# 407-exp.net
KiCad netlist of a schematic drawn in Altium Designer
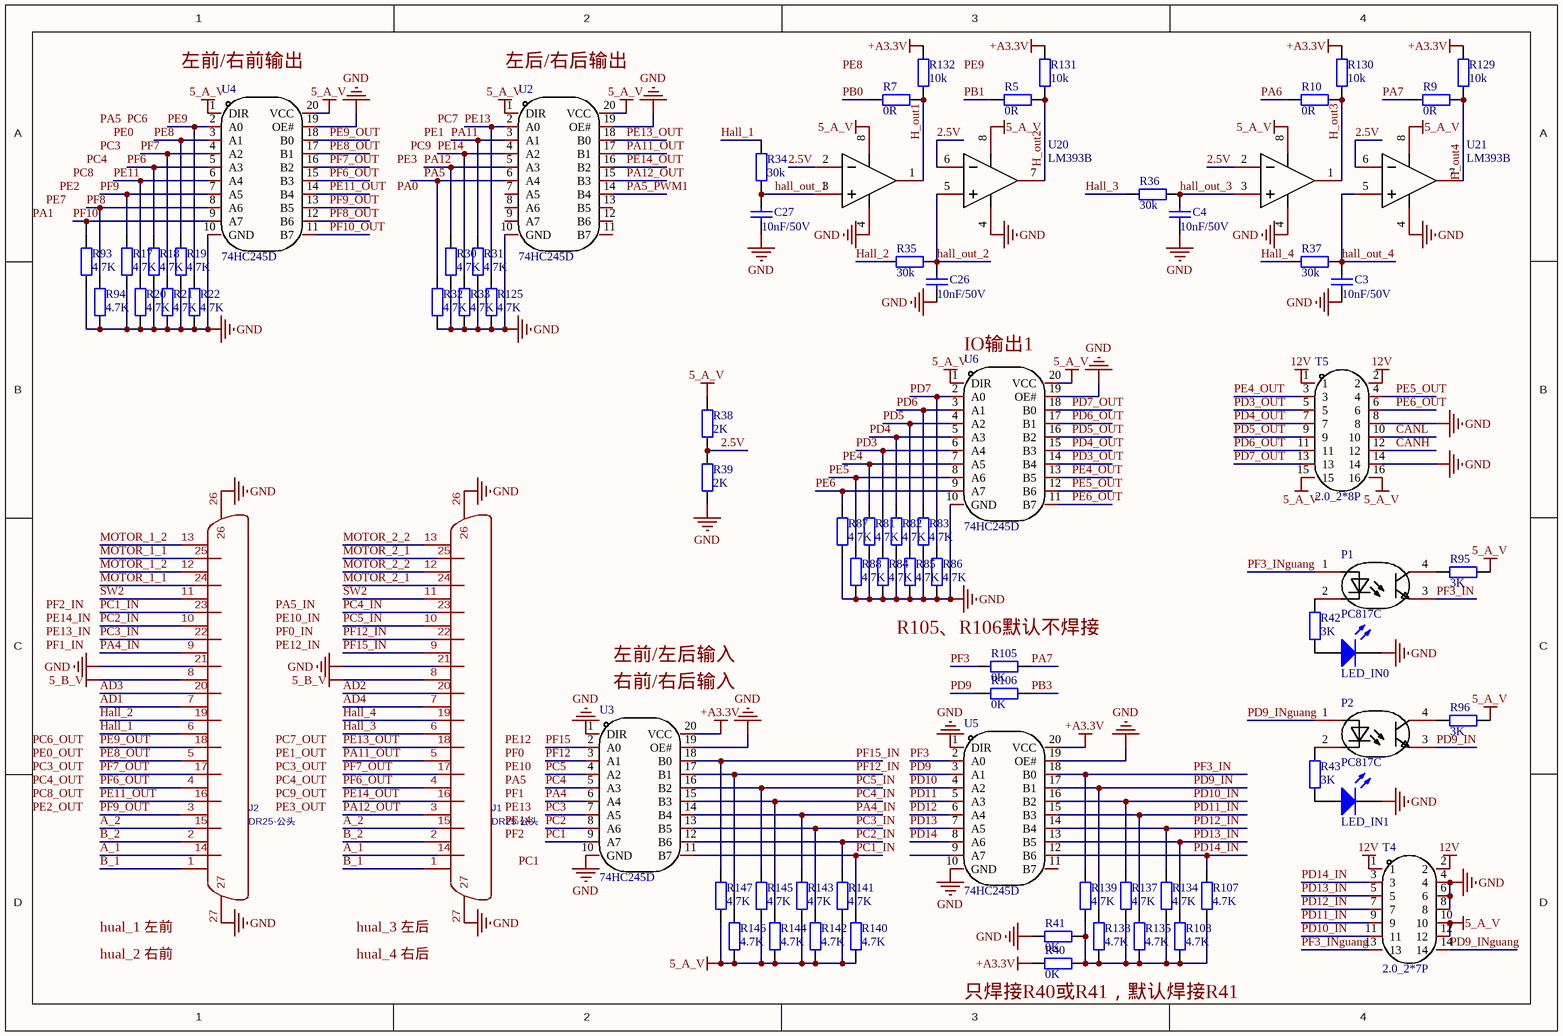
[diagram p0: 407-exp.schdoc]

(export (version "E")
  (design (tool "Eeschema 10.0.6"))
  (components
    (comp (ref "C3")
      (value "10nF/50V")
      (description "Capacitor")
      (fields (field (name "PUBLISHER") "Altium Limited"))
      (libsource (lib "Miscellaneous Devices") (part "Cap"))
    )
    (comp (ref "C4")
      (value "10nF/50V")
      (description "Capacitor")
      (fields (field (name "PUBLISHER") "Altium Limited"))
      (libsource (lib "Miscellaneous Devices") (part "Cap"))
    )
    (comp (ref "C26")
      (value "10nF/50V")
      (description "Capacitor")
      (fields (field (name "PUBLISHER") "Altium Limited"))
      (libsource (lib "Miscellaneous Devices") (part "Cap"))
    )
    (comp (ref "C27")
      (value "10nF/50V")
      (description "Capacitor")
      (fields (field (name "PUBLISHER") "Altium Limited"))
      (libsource (lib "Miscellaneous Devices") (part "Cap"))
    )
    (comp (ref "J1")
      (value "DR25-公头")
      (fields (field (name "MANUFACTURER PART") "DMR025PF000XH00") (field (name "CONTRIBUTOR") "MR_Peng888"))
      (libsource (lib "altium-import") (part "root_1_DR25-公头_"))
    )
    (comp (ref "J2")
      (value "DR25-公头")
      (fields (field (name "MANUFACTURER PART") "DMR025PF000XH00") (field (name "CONTRIBUTOR") "MR_Peng888"))
      (libsource (lib "altium-import") (part "root_1_DR25-公头_"))
    )
    (comp (ref "LED_IN0")
      (value "LED")
      (footprint "LED")
      (description "发光二极管")
      (libsource (lib "0.3 - LED发光二极管-IR二极管_接收管-光耦") (part "LED"))
    )
    (comp (ref "LED_IN1")
      (value "LED")
      (footprint "LED")
      (description "发光二极管")
      (libsource (lib "0.3 - LED发光二极管-IR二极管_接收管-光耦") (part "LED"))
    )
    (comp (ref "P1") (value "PC817C") (footprint "PC817C") (libsource (lib "tianjin_2023") (part "PC817C")))
    (comp (ref "P2") (value "PC817C") (footprint "PC817C") (libsource (lib "tianjin_2023") (part "PC817C")))
    (comp (ref "R5")
      (value "0R")
      (footprint "R0603_L")
      (description "Resistor")
      (fields (field (name "PUBLISHER") "Altium Limited"))
      (libsource (lib "MOS motor driving module ") (part "Res2"))
    )
    (comp (ref "R7")
      (value "0R")
      (footprint "R0603_L")
      (description "Resistor")
      (fields (field (name "PUBLISHER") "Altium Limited"))
      (libsource (lib "MOS motor driving module ") (part "Res2"))
    )
    (comp (ref "R9")
      (value "0R")
      (footprint "R0603_L")
      (description "Resistor")
      (fields (field (name "PUBLISHER") "Altium Limited"))
      (libsource (lib "MOS motor driving module ") (part "Res2"))
    )
    (comp (ref "R10")
      (value "0R")
      (footprint "R0603_L")
      (description "Resistor")
      (fields (field (name "PUBLISHER") "Altium Limited"))
      (libsource (lib "MOS motor driving module ") (part "Res2"))
    )
    (comp (ref "R17")
      (value "4.7K")
      (footprint "R0603_L")
      (description "Resistor")
      (fields (field (name "PUBLISHER") "Altium Limited"))
      (libsource (lib "") (part "Res2_1"))
    )
    (comp (ref "R18")
      (value "4.7K")
      (footprint "R0603_L")
      (description "Resistor")
      (fields (field (name "PUBLISHER") "Altium Limited"))
      (libsource (lib "") (part "Res2_1"))
    )
    (comp (ref "R19")
      (value "4.7K")
      (footprint "R0603_L")
      (description "Resistor")
      (fields (field (name "PUBLISHER") "Altium Limited"))
      (libsource (lib "") (part "Res2_1"))
    )
    (comp (ref "R20")
      (value "4.7K")
      (footprint "R0603_L")
      (description "Resistor")
      (fields (field (name "PUBLISHER") "Altium Limited"))
      (libsource (lib "") (part "Res2_1"))
    )
    (comp (ref "R21")
      (value "4.7K")
      (footprint "R0603_L")
      (description "Resistor")
      (fields (field (name "PUBLISHER") "Altium Limited"))
      (libsource (lib "") (part "Res2_1"))
    )
    (comp (ref "R22")
      (value "4.7K")
      (footprint "R0603_L")
      (description "Resistor")
      (fields (field (name "PUBLISHER") "Altium Limited"))
      (libsource (lib "") (part "Res2_1"))
    )
    (comp (ref "R30")
      (value "4.7K")
      (footprint "R0603_L")
      (description "Resistor")
      (fields (field (name "PUBLISHER") "Altium Limited"))
      (libsource (lib "") (part "Res2_1"))
    )
    (comp (ref "R31")
      (value "4.7K")
      (footprint "R0603_L")
      (description "Resistor")
      (fields (field (name "PUBLISHER") "Altium Limited"))
      (libsource (lib "") (part "Res2_1"))
    )
    (comp (ref "R32")
      (value "4.7K")
      (footprint "R0603_L")
      (description "Resistor")
      (fields (field (name "PUBLISHER") "Altium Limited"))
      (libsource (lib "") (part "Res2_1"))
    )
    (comp (ref "R33")
      (value "4.7K")
      (footprint "R0603_L")
      (description "Resistor")
      (fields (field (name "PUBLISHER") "Altium Limited"))
      (libsource (lib "") (part "Res2_1"))
    )
    (comp (ref "R34")
      (value "30k")
      (footprint "R0603_L")
      (description "Resistor")
      (fields (field (name "PUBLISHER") "Altium Limited"))
      (libsource (lib "") (part "Res2_2"))
    )
    (comp (ref "R35")
      (value "30k")
      (footprint "R0603_L")
      (description "Resistor")
      (fields (field (name "PUBLISHER") "Altium Limited"))
      (libsource (lib "MOS motor driving module ") (part "Res2"))
    )
    (comp (ref "R36")
      (value "30k")
      (footprint "R0603_L")
      (description "Resistor")
      (fields (field (name "PUBLISHER") "Altium Limited"))
      (libsource (lib "MOS motor driving module ") (part "Res2"))
    )
    (comp (ref "R37")
      (value "30k")
      (footprint "R0603_L")
      (description "Resistor")
      (fields (field (name "PUBLISHER") "Altium Limited"))
      (libsource (lib "MOS motor driving module ") (part "Res2"))
    )
    (comp (ref "R38")
      (value "2K")
      (description "Resistor")
      (fields (field (name "PUBLISHER") "Altium Limited"))
      (libsource (lib "") (part "Res2_2"))
    )
    (comp (ref "R39")
      (value "2K")
      (description "Resistor")
      (fields (field (name "PUBLISHER") "Altium Limited"))
      (libsource (lib "") (part "Res2_2"))
    )
    (comp (ref "R40")
      (value "0K")
      (footprint "R0603_L")
      (description "Resistor")
      (fields (field (name "PUBLISHER") "Altium Limited"))
      (libsource (lib "MOS motor driving module ") (part "Res2"))
    )
    (comp (ref "R41")
      (value "0K")
      (footprint "R0603_L")
      (description "Resistor")
      (fields (field (name "PUBLISHER") "Altium Limited"))
      (libsource (lib "MOS motor driving module ") (part "Res2"))
    )
    (comp (ref "R42")
      (value "3K")
      (description "Resistor")
      (fields (field (name "PUBLISHER") "Altium Limited"))
      (libsource (lib "") (part "Res2_1"))
    )
    (comp (ref "R43")
      (value "3K")
      (description "Resistor")
      (fields (field (name "PUBLISHER") "Altium Limited"))
      (libsource (lib "") (part "Res2_1"))
    )
    (comp (ref "R81")
      (value "4.7K")
      (description "Resistor")
      (fields (field (name "PUBLISHER") "Altium Limited"))
      (libsource (lib "") (part "Res2_1"))
    )
    (comp (ref "R82")
      (value "4.7K")
      (description "Resistor")
      (fields (field (name "PUBLISHER") "Altium Limited"))
      (libsource (lib "") (part "Res2_1"))
    )
    (comp (ref "R83")
      (value "4.7K")
      (description "Resistor")
      (fields (field (name "PUBLISHER") "Altium Limited"))
      (libsource (lib "") (part "Res2_1"))
    )
    (comp (ref "R84")
      (value "4.7K")
      (description "Resistor")
      (fields (field (name "PUBLISHER") "Altium Limited"))
      (libsource (lib "") (part "Res2_1"))
    )
    (comp (ref "R85")
      (value "4.7K")
      (description "Resistor")
      (fields (field (name "PUBLISHER") "Altium Limited"))
      (libsource (lib "") (part "Res2_1"))
    )
    (comp (ref "R86")
      (value "4.7K")
      (description "Resistor")
      (fields (field (name "PUBLISHER") "Altium Limited"))
      (libsource (lib "") (part "Res2_1"))
    )
    (comp (ref "R87")
      (value "4.7K")
      (description "Resistor")
      (fields (field (name "PUBLISHER") "Altium Limited"))
      (libsource (lib "") (part "Res2_1"))
    )
    (comp (ref "R88")
      (value "4.7K")
      (description "Resistor")
      (fields (field (name "PUBLISHER") "Altium Limited"))
      (libsource (lib "") (part "Res2_1"))
    )
    (comp (ref "R93")
      (value "4.7K")
      (footprint "R0603_L")
      (description "Resistor")
      (fields (field (name "PUBLISHER") "Altium Limited"))
      (libsource (lib "") (part "Res2_1"))
    )
    (comp (ref "R94")
      (value "4.7K")
      (footprint "R0603_L")
      (description "Resistor")
      (fields (field (name "PUBLISHER") "Altium Limited"))
      (libsource (lib "") (part "Res2_1"))
    )
    (comp (ref "R95")
      (value "3K")
      (description "Resistor")
      (fields (field (name "PUBLISHER") "Altium Limited"))
      (libsource (lib "MOS motor driving module ") (part "Res2"))
    )
    (comp (ref "R96")
      (value "3K")
      (description "Resistor")
      (fields (field (name "PUBLISHER") "Altium Limited"))
      (libsource (lib "MOS motor driving module ") (part "Res2"))
    )
    (comp (ref "R105")
      (value "0K")
      (footprint "R0603_L")
      (description "Resistor")
      (fields (field (name "PUBLISHER") "Altium Limited"))
      (libsource (lib "") (part "Res2_3"))
    )
    (comp (ref "R106")
      (value "0K")
      (footprint "R0603_L")
      (description "Resistor")
      (fields (field (name "PUBLISHER") "Altium Limited"))
      (libsource (lib "") (part "Res2_3"))
    )
    (comp (ref "R107")
      (value "4.7K")
      (description "Resistor")
      (fields (field (name "PUBLISHER") "Altium Limited"))
      (libsource (lib "") (part "Res2_1"))
    )
    (comp (ref "R108")
      (value "4.7K")
      (description "Resistor")
      (fields (field (name "PUBLISHER") "Altium Limited"))
      (libsource (lib "") (part "Res2_1"))
    )
    (comp (ref "R125")
      (value "4.7K")
      (footprint "R0603_L")
      (description "Resistor")
      (fields (field (name "PUBLISHER") "Altium Limited"))
      (libsource (lib "") (part "Res2_1"))
    )
    (comp (ref "R129")
      (value "10k")
      (footprint "R0603_L")
      (description "Resistor")
      (fields (field (name "PUBLISHER") "Altium Limited"))
      (libsource (lib "") (part "Res2_2"))
    )
    (comp (ref "R130")
      (value "10k")
      (footprint "R0603_L")
      (description "Resistor")
      (fields (field (name "PUBLISHER") "Altium Limited"))
      (libsource (lib "") (part "Res2_2"))
    )
    (comp (ref "R131")
      (value "10k")
      (footprint "R0603_L")
      (description "Resistor")
      (fields (field (name "PUBLISHER") "Altium Limited"))
      (libsource (lib "") (part "Res2_2"))
    )
    (comp (ref "R132")
      (value "10k")
      (footprint "R0603_L")
      (description "Resistor")
      (fields (field (name "PUBLISHER") "Altium Limited"))
      (libsource (lib "") (part "Res2_2"))
    )
    (comp (ref "R134")
      (value "4.7K")
      (description "Resistor")
      (fields (field (name "PUBLISHER") "Altium Limited"))
      (libsource (lib "") (part "Res2_1"))
    )
    (comp (ref "R135")
      (value "4.7K")
      (description "Resistor")
      (fields (field (name "PUBLISHER") "Altium Limited"))
      (libsource (lib "") (part "Res2_1"))
    )
    (comp (ref "R137")
      (value "4.7K")
      (description "Resistor")
      (fields (field (name "PUBLISHER") "Altium Limited"))
      (libsource (lib "") (part "Res2_1"))
    )
    (comp (ref "R138")
      (value "4.7K")
      (description "Resistor")
      (fields (field (name "PUBLISHER") "Altium Limited"))
      (libsource (lib "") (part "Res2_1"))
    )
    (comp (ref "R139")
      (value "4.7K")
      (description "Resistor")
      (fields (field (name "PUBLISHER") "Altium Limited"))
      (libsource (lib "") (part "Res2_1"))
    )
    (comp (ref "R140")
      (value "4.7K")
      (footprint "R0603_L")
      (description "Resistor")
      (fields (field (name "PUBLISHER") "Altium Limited"))
      (libsource (lib "") (part "Res2_1"))
    )
    (comp (ref "R141")
      (value "4.7K")
      (footprint "R0603_L")
      (description "Resistor")
      (fields (field (name "PUBLISHER") "Altium Limited"))
      (libsource (lib "") (part "Res2_1"))
    )
    (comp (ref "R142")
      (value "4.7K")
      (footprint "R0603_L")
      (description "Resistor")
      (fields (field (name "PUBLISHER") "Altium Limited"))
      (libsource (lib "") (part "Res2_1"))
    )
    (comp (ref "R143")
      (value "4.7K")
      (footprint "R0603_L")
      (description "Resistor")
      (fields (field (name "PUBLISHER") "Altium Limited"))
      (libsource (lib "") (part "Res2_1"))
    )
    (comp (ref "R144")
      (value "4.7K")
      (footprint "R0603_L")
      (description "Resistor")
      (fields (field (name "PUBLISHER") "Altium Limited"))
      (libsource (lib "") (part "Res2_1"))
    )
    (comp (ref "R145")
      (value "4.7K")
      (footprint "R0603_L")
      (description "Resistor")
      (fields (field (name "PUBLISHER") "Altium Limited"))
      (libsource (lib "") (part "Res2_1"))
    )
    (comp (ref "R146")
      (value "4.7K")
      (footprint "R0603_L")
      (description "Resistor")
      (fields (field (name "PUBLISHER") "Altium Limited"))
      (libsource (lib "") (part "Res2_1"))
    )
    (comp (ref "R147")
      (value "4.7K")
      (footprint "R0603_L")
      (description "Resistor")
      (fields (field (name "PUBLISHER") "Altium Limited"))
      (libsource (lib "") (part "Res2_1"))
    )
    (comp (ref "T4")
      (value "2.0_2*7P")
      (footprint "2.0_2*7P")
      (libsource (lib "tianjin_2023") (part "2.0_2*7P"))
    )
    (comp (ref "T5")
      (value "2.0_2*8P")
      (footprint "2.0_2*8P")
      (libsource (lib "tianjin_2023") (part "2.0_2*8P"))
    )
    (comp (ref "U2")
      (value "74HC245D")
      (footprint "74HC245D")
      (libsource (lib "tianjin_2023") (part "74HC245D"))
    )
    (comp (ref "U3")
      (value "74HC245D")
      (footprint "74HC245D")
      (libsource (lib "tianjin_2023") (part "74HC245D"))
    )
    (comp (ref "U4")
      (value "74HC245D")
      (footprint "74HC245D")
      (libsource (lib "tianjin_2023") (part "74HC245D"))
    )
    (comp (ref "U5")
      (value "74HC245D")
      (footprint "74HC245D")
      (libsource (lib "tianjin_2023") (part "74HC245D"))
    )
    (comp (ref "U6")
      (value "74HC245D")
      (footprint "74HC245D")
      (libsource (lib "tianjin_2023") (part "74HC245D"))
    )
    (comp (ref "U20") (value "LM393B") (footprint "LM393B") (libsource (lib "tianjin_2023") (part "LM393B")))
    (comp (ref "U21") (value "LM393B") (footprint "LM393B") (libsource (lib "tianjin_2023") (part "LM393B")))
  )
  (nets
    (net (code "1") (name "+A3.3V") (class "Default")
      (node (ref "R129") (pin "1") (pinfunction "1_1") (pintype "passive"))
      (node (ref "R130") (pin "1") (pinfunction "1_1") (pintype "passive"))
      (node (ref "R131") (pin "1") (pinfunction "1_1") (pintype "passive"))
      (node (ref "R132") (pin "1") (pinfunction "1_1") (pintype "passive"))
      (node (ref "R40") (pin "1") (pinfunction "1_1") (pintype "passive"))
      (node (ref "U3") (pin "20") (pinfunction "VCC_20") (pintype "passive"))
      (node (ref "U5") (pin "20") (pinfunction "VCC_20") (pintype "passive"))
    )
    (net (code "2") (name "/2.5V") (class "Default")
      (node (ref "R38") (pin "2") (pinfunction "2_2") (pintype "passive"))
      (node (ref "R39") (pin "1") (pinfunction "1_1") (pintype "passive"))
      (node (ref "U20") (pin "2") (pinfunction "1IN-_2") (pintype "passive"))
      (node (ref "U20") (pin "6") (pinfunction "1IN-_6") (pintype "passive"))
      (node (ref "U21") (pin "2") (pinfunction "1IN-_2") (pintype "passive"))
      (node (ref "U21") (pin "6") (pinfunction "1IN-_6") (pintype "passive"))
    )
    (net (code "3") (name "/AD1") (class "Default")
      (node (ref "J2") (pin "7") (pinfunction "7_7") (pintype "passive"))
    )
    (net (code "4") (name "/AD2") (class "Default")
      (node (ref "J1") (pin "20") (pinfunction "20_20") (pintype "passive"))
    )
    (net (code "5") (name "/AD3") (class "Default")
      (node (ref "J2") (pin "20") (pinfunction "20_20") (pintype "passive"))
    )
    (net (code "6") (name "/AD4") (class "Default")
      (node (ref "J1") (pin "7") (pinfunction "7_7") (pintype "passive"))
    )
    (net (code "7") (name "/A_1") (class "Default")
      (node (ref "J1") (pin "14") (pinfunction "14_14") (pintype "passive"))
      (node (ref "J2") (pin "14") (pinfunction "14_14") (pintype "passive"))
    )
    (net (code "8") (name "/A_2") (class "Default")
      (node (ref "J1") (pin "15") (pinfunction "15_15") (pintype "passive"))
      (node (ref "J2") (pin "15") (pinfunction "15_15") (pintype "passive"))
    )
    (net (code "9") (name "/B_1") (class "Default")
      (node (ref "J1") (pin "1") (pinfunction "1_1") (pintype "passive"))
      (node (ref "J2") (pin "1") (pinfunction "1_1") (pintype "passive"))
    )
    (net (code "10") (name "/B_2") (class "Default")
      (node (ref "J1") (pin "2") (pinfunction "2_2") (pintype "passive"))
      (node (ref "J2") (pin "2") (pinfunction "2_2") (pintype "passive"))
    )
    (net (code "11") (name "/CANH") (class "Default")
      (node (ref "T5") (pin "12") (pinfunction "12_12") (pintype "passive"))
    )
    (net (code "12") (name "/CANL") (class "Default")
      (node (ref "T5") (pin "10") (pinfunction "10_10") (pintype "passive"))
    )
    (net (code "13") (name "/H_out1") (class "Default")
      (node (ref "R132") (pin "2") (pinfunction "2_2") (pintype "passive"))
      (node (ref "R7") (pin "2") (pinfunction "2_2") (pintype "passive"))
      (node (ref "U20") (pin "1") (pinfunction "1OUT_1") (pintype "passive"))
    )
    (net (code "14") (name "/H_out2") (class "Default")
      (node (ref "R131") (pin "2") (pinfunction "2_2") (pintype "passive"))
      (node (ref "R5") (pin "2") (pinfunction "2_2") (pintype "passive"))
      (node (ref "U20") (pin "7") (pinfunction "1OUT_7") (pintype "passive"))
    )
    (net (code "15") (name "/H_out3") (class "Default")
      (node (ref "R10") (pin "2") (pinfunction "2_2") (pintype "passive"))
      (node (ref "R130") (pin "2") (pinfunction "2_2") (pintype "passive"))
      (node (ref "U21") (pin "1") (pinfunction "1OUT_1") (pintype "passive"))
    )
    (net (code "16") (name "/H_out4") (class "Default")
      (node (ref "R129") (pin "2") (pinfunction "2_2") (pintype "passive"))
      (node (ref "R9") (pin "2") (pinfunction "2_2") (pintype "passive"))
      (node (ref "U21") (pin "7") (pinfunction "1OUT_7") (pintype "passive"))
    )
    (net (code "17") (name "/Hall_1") (class "Default")
      (node (ref "J2") (pin "6") (pinfunction "6_6") (pintype "passive"))
      (node (ref "R34") (pin "1") (pinfunction "1_1") (pintype "passive"))
    )
    (net (code "18") (name "/Hall_2") (class "Default")
      (node (ref "J2") (pin "19") (pinfunction "19_19") (pintype "passive"))
      (node (ref "R35") (pin "1") (pinfunction "1_1") (pintype "passive"))
    )
    (net (code "19") (name "/Hall_3") (class "Default")
      (node (ref "J1") (pin "6") (pinfunction "6_6") (pintype "passive"))
      (node (ref "R36") (pin "1") (pinfunction "1_1") (pintype "passive"))
    )
    (net (code "20") (name "/Hall_4") (class "Default")
      (node (ref "J1") (pin "19") (pinfunction "19_19") (pintype "passive"))
      (node (ref "R37") (pin "1") (pinfunction "1_1") (pintype "passive"))
    )
    (net (code "21") (name "/MOTOR_1_1") (class "Default")
      (node (ref "J2") (pin "24") (pinfunction "24_24") (pintype "passive"))
      (node (ref "J2") (pin "25") (pinfunction "25_25") (pintype "passive"))
    )
    (net (code "22") (name "/MOTOR_1_2") (class "Default")
      (node (ref "J2") (pin "12") (pinfunction "12_12") (pintype "passive"))
      (node (ref "J2") (pin "13") (pinfunction "13_13") (pintype "passive"))
    )
    (net (code "23") (name "/MOTOR_2_1") (class "Default")
      (node (ref "J1") (pin "24") (pinfunction "24_24") (pintype "passive"))
      (node (ref "J1") (pin "25") (pinfunction "25_25") (pintype "passive"))
    )
    (net (code "24") (name "/MOTOR_2_2") (class "Default")
      (node (ref "J1") (pin "12") (pinfunction "12_12") (pintype "passive"))
      (node (ref "J1") (pin "13") (pinfunction "13_13") (pintype "passive"))
    )
    (net (code "27") (name "/PA4") (class "Default")
      (node (ref "U3") (pin "6") (pinfunction "A4_6") (pintype "passive"))
    )
    (net (code "28") (name "/PA4_IN") (class "Default")
      (node (ref "J2") (pin "9") (pinfunction "9_9") (pintype "passive"))
      (node (ref "R143") (pin "2") (pinfunction "2_2") (pintype "passive"))
      (node (ref "U3") (pin "14") (pinfunction "B4_14") (pintype "passive"))
    )
    (net (code "29") (name "/PA5") (class "Default")
      (node (ref "R32") (pin "2") (pinfunction "2_2") (pintype "passive"))
      (node (ref "U2") (pin "6") (pinfunction "A4_6") (pintype "passive"))
    )
    (net (code "31") (name "/PA5_PWM1") (class "Default")
      (node (ref "U2") (pin "14") (pinfunction "B4_14") (pintype "passive"))
    )
    (net (code "32") (name "/PA6") (class "Default")
      (node (ref "R10") (pin "1") (pinfunction "1_1") (pintype "passive"))
    )
    (net (code "33") (name "/PA7") (class "Default")
      (node (ref "R105") (pin "1") (pinfunction "1_1") (pintype "passive"))
      (node (ref "R9") (pin "1") (pinfunction "1_1") (pintype "passive"))
    )
    (net (code "34") (name "/PA11") (class "Default")
      (node (ref "R31") (pin "2") (pinfunction "2_2") (pintype "passive"))
      (node (ref "U2") (pin "3") (pinfunction "A1_3") (pintype "passive"))
    )
    (net (code "35") (name "/PA11_OUT") (class "Default")
      (node (ref "J1") (pin "5") (pinfunction "5_5") (pintype "passive"))
      (node (ref "U2") (pin "17") (pinfunction "B1_17") (pintype "passive"))
    )
    (net (code "36") (name "/PA12") (class "Default")
      (node (ref "R30") (pin "2") (pinfunction "2_2") (pintype "passive"))
      (node (ref "U2") (pin "5") (pinfunction "A3_5") (pintype "passive"))
    )
    (net (code "37") (name "/PA12_OUT") (class "Default")
      (node (ref "J1") (pin "3") (pinfunction "3_3") (pintype "passive"))
      (node (ref "U2") (pin "15") (pinfunction "B3_15") (pintype "passive"))
    )
    (net (code "38") (name "/PB0") (class "Default")
      (node (ref "R7") (pin "1") (pinfunction "1_1") (pintype "passive"))
    )
    (net (code "39") (name "/PB1") (class "Default")
      (node (ref "R5") (pin "1") (pinfunction "1_1") (pintype "passive"))
    )
    (net (code "40") (name "/PB3") (class "Default")
      (node (ref "R106") (pin "1") (pinfunction "1_1") (pintype "passive"))
    )
    (net (code "41") (name "/PC1") (class "Default")
      (node (ref "U3") (pin "9") (pinfunction "A7_9") (pintype "passive"))
    )
    (net (code "42") (name "/PC1_IN") (class "Default")
      (node (ref "J2") (pin "23") (pinfunction "23_23") (pintype "passive"))
      (node (ref "R140") (pin "2") (pinfunction "2_2") (pintype "passive"))
      (node (ref "U3") (pin "11") (pinfunction "B7_11") (pintype "passive"))
    )
    (net (code "43") (name "/PC2") (class "Default")
      (node (ref "U3") (pin "8") (pinfunction "A6_8") (pintype "passive"))
    )
    (net (code "44") (name "/PC2_IN") (class "Default")
      (node (ref "J2") (pin "10") (pinfunction "10_10") (pintype "passive"))
      (node (ref "R141") (pin "2") (pinfunction "2_2") (pintype "passive"))
      (node (ref "U3") (pin "12") (pinfunction "B6_12") (pintype "passive"))
    )
    (net (code "45") (name "/PC3") (class "Default")
      (node (ref "U3") (pin "7") (pinfunction "A5_7") (pintype "passive"))
    )
    (net (code "46") (name "/PC3_IN") (class "Default")
      (node (ref "J2") (pin "22") (pinfunction "22_22") (pintype "passive"))
      (node (ref "R142") (pin "2") (pinfunction "2_2") (pintype "passive"))
      (node (ref "U3") (pin "13") (pinfunction "B5_13") (pintype "passive"))
    )
    (net (code "48") (name "/PC4") (class "Default")
      (node (ref "U3") (pin "5") (pinfunction "A3_5") (pintype "passive"))
    )
    (net (code "49") (name "/PC4_IN") (class "Default")
      (node (ref "J1") (pin "23") (pinfunction "23_23") (pintype "passive"))
      (node (ref "R144") (pin "2") (pinfunction "2_2") (pintype "passive"))
      (node (ref "U3") (pin "15") (pinfunction "B3_15") (pintype "passive"))
    )
    (net (code "51") (name "/PC5") (class "Default")
      (node (ref "U3") (pin "4") (pinfunction "A2_4") (pintype "passive"))
    )
    (net (code "52") (name "/PC5_IN") (class "Default")
      (node (ref "J1") (pin "10") (pinfunction "10_10") (pintype "passive"))
      (node (ref "R145") (pin "2") (pinfunction "2_2") (pintype "passive"))
      (node (ref "U3") (pin "16") (pinfunction "B2_16") (pintype "passive"))
    )
    (net (code "61") (name "/PD3") (class "Default")
      (node (ref "R84") (pin "2") (pinfunction "2_2") (pintype "passive"))
      (node (ref "U6") (pin "6") (pinfunction "A4_6") (pintype "passive"))
    )
    (net (code "62") (name "/PD3_OUT") (class "Default")
      (node (ref "T5") (pin "5") (pinfunction "5_5") (pintype "passive"))
      (node (ref "U6") (pin "14") (pinfunction "B4_14") (pintype "passive"))
    )
    (net (code "63") (name "/PD4") (class "Default")
      (node (ref "R82") (pin "2") (pinfunction "2_2") (pintype "passive"))
      (node (ref "U6") (pin "5") (pinfunction "A3_5") (pintype "passive"))
    )
    (net (code "64") (name "/PD4_OUT") (class "Default")
      (node (ref "T5") (pin "7") (pinfunction "7_7") (pintype "passive"))
      (node (ref "U6") (pin "15") (pinfunction "B3_15") (pintype "passive"))
    )
    (net (code "65") (name "/PD5") (class "Default")
      (node (ref "R85") (pin "2") (pinfunction "2_2") (pintype "passive"))
      (node (ref "U6") (pin "4") (pinfunction "A2_4") (pintype "passive"))
    )
    (net (code "66") (name "/PD5_OUT") (class "Default")
      (node (ref "T5") (pin "9") (pinfunction "9_9") (pintype "passive"))
      (node (ref "U6") (pin "16") (pinfunction "B2_16") (pintype "passive"))
    )
    (net (code "67") (name "/PD6") (class "Default")
      (node (ref "R83") (pin "2") (pinfunction "2_2") (pintype "passive"))
      (node (ref "U6") (pin "3") (pinfunction "A1_3") (pintype "passive"))
    )
    (net (code "68") (name "/PD6_OUT") (class "Default")
      (node (ref "T5") (pin "11") (pinfunction "11_11") (pintype "passive"))
      (node (ref "U6") (pin "17") (pinfunction "B1_17") (pintype "passive"))
    )
    (net (code "69") (name "/PD7") (class "Default")
      (node (ref "R86") (pin "2") (pinfunction "2_2") (pintype "passive"))
      (node (ref "U6") (pin "2") (pinfunction "A0_2") (pintype "passive"))
    )
    (net (code "70") (name "/PD7_OUT") (class "Default")
      (node (ref "T5") (pin "13") (pinfunction "13_13") (pintype "passive"))
      (node (ref "U6") (pin "18") (pinfunction "B0_18") (pintype "passive"))
    )
    (net (code "71") (name "/PD9") (class "Default")
      (node (ref "R106") (pin "2") (pinfunction "2_2") (pintype "passive"))
      (node (ref "U5") (pin "3") (pinfunction "A1_3") (pintype "passive"))
    )
    (net (code "72") (name "/PD9_IN") (class "Default")
      (node (ref "P2") (pin "3") (pinfunction "3_3") (pintype "passive"))
      (node (ref "R138") (pin "2") (pinfunction "2_2") (pintype "passive"))
      (node (ref "U5") (pin "17") (pinfunction "B1_17") (pintype "passive"))
    )
    (net (code "73") (name "/PD9_INguang") (class "Default")
      (node (ref "P2") (pin "1") (pinfunction "1_1") (pintype "passive"))
      (node (ref "T4") (pin "14") (pinfunction "14_14") (pintype "passive"))
    )
    (net (code "74") (name "/PD10") (class "Default")
      (node (ref "U5") (pin "4") (pinfunction "A2_4") (pintype "passive"))
    )
    (net (code "75") (name "/PD10_IN") (class "Default")
      (node (ref "R137") (pin "2") (pinfunction "2_2") (pintype "passive"))
      (node (ref "T4") (pin "11") (pinfunction "11_11") (pintype "passive"))
      (node (ref "U5") (pin "16") (pinfunction "B2_16") (pintype "passive"))
    )
    (net (code "76") (name "/PD11") (class "Default")
      (node (ref "U5") (pin "5") (pinfunction "A3_5") (pintype "passive"))
    )
    (net (code "77") (name "/PD11_IN") (class "Default")
      (node (ref "R135") (pin "2") (pinfunction "2_2") (pintype "passive"))
      (node (ref "T4") (pin "9") (pinfunction "9_9") (pintype "passive"))
      (node (ref "U5") (pin "15") (pinfunction "B3_15") (pintype "passive"))
    )
    (net (code "78") (name "/PD12") (class "Default")
      (node (ref "U5") (pin "6") (pinfunction "A4_6") (pintype "passive"))
    )
    (net (code "79") (name "/PD12_IN") (class "Default")
      (node (ref "R134") (pin "2") (pinfunction "2_2") (pintype "passive"))
      (node (ref "T4") (pin "7") (pinfunction "7_7") (pintype "passive"))
      (node (ref "U5") (pin "14") (pinfunction "B4_14") (pintype "passive"))
    )
    (net (code "80") (name "/PD13") (class "Default")
      (node (ref "U5") (pin "7") (pinfunction "A5_7") (pintype "passive"))
    )
    (net (code "81") (name "/PD13_IN") (class "Default")
      (node (ref "R108") (pin "2") (pinfunction "2_2") (pintype "passive"))
      (node (ref "T4") (pin "5") (pinfunction "5_5") (pintype "passive"))
      (node (ref "U5") (pin "13") (pinfunction "B5_13") (pintype "passive"))
    )
    (net (code "82") (name "/PD14") (class "Default")
      (node (ref "U5") (pin "8") (pinfunction "A6_8") (pintype "passive"))
    )
    (net (code "83") (name "/PD14_IN") (class "Default")
      (node (ref "R107") (pin "2") (pinfunction "2_2") (pintype "passive"))
      (node (ref "T4") (pin "3") (pinfunction "3_3") (pintype "passive"))
      (node (ref "U5") (pin "12") (pinfunction "B6_12") (pintype "passive"))
    )
    (net (code "92") (name "/PE4") (class "Default")
      (node (ref "R81") (pin "2") (pinfunction "2_2") (pintype "passive"))
      (node (ref "U6") (pin "7") (pinfunction "A5_7") (pintype "passive"))
    )
    (net (code "93") (name "/PE4_OUT") (class "Default")
      (node (ref "T5") (pin "3") (pinfunction "3_3") (pintype "passive"))
      (node (ref "U6") (pin "13") (pinfunction "B5_13") (pintype "passive"))
    )
    (net (code "94") (name "/PE5") (class "Default")
      (node (ref "R88") (pin "2") (pinfunction "2_2") (pintype "passive"))
      (node (ref "U6") (pin "8") (pinfunction "A6_8") (pintype "passive"))
    )
    (net (code "95") (name "/PE5_OUT") (class "Default")
      (node (ref "T5") (pin "4") (pinfunction "4_4") (pintype "passive"))
      (node (ref "U6") (pin "12") (pinfunction "B6_12") (pintype "passive"))
    )
    (net (code "96") (name "/PE6") (class "Default")
      (node (ref "R87") (pin "2") (pinfunction "2_2") (pintype "passive"))
      (node (ref "U6") (pin "9") (pinfunction "A7_9") (pintype "passive"))
    )
    (net (code "97") (name "/PE6_OUT") (class "Default")
      (node (ref "T5") (pin "6") (pinfunction "6_6") (pintype "passive"))
      (node (ref "U6") (pin "11") (pinfunction "B7_11") (pintype "passive"))
    )
    (net (code "99") (name "/PE8") (class "Default")
      (node (ref "R19") (pin "2") (pinfunction "2_2") (pintype "passive"))
      (node (ref "U4") (pin "3") (pinfunction "A1_3") (pintype "passive"))
    )
    (net (code "100") (name "/PE8_OUT") (class "Default")
      (node (ref "J2") (pin "5") (pinfunction "5_5") (pintype "passive"))
      (node (ref "U4") (pin "17") (pinfunction "B1_17") (pintype "passive"))
    )
    (net (code "101") (name "/PE9") (class "Default")
      (node (ref "R22") (pin "2") (pinfunction "2_2") (pintype "passive"))
      (node (ref "U4") (pin "2") (pinfunction "A0_2") (pintype "passive"))
    )
    (net (code "102") (name "/PE9_OUT") (class "Default")
      (node (ref "J2") (pin "18") (pinfunction "18_18") (pintype "passive"))
      (node (ref "U4") (pin "18") (pinfunction "B0_18") (pintype "passive"))
    )
    (net (code "105") (name "/PE11") (class "Default")
      (node (ref "R20") (pin "2") (pinfunction "2_2") (pintype "passive"))
      (node (ref "U4") (pin "6") (pinfunction "A4_6") (pintype "passive"))
    )
    (net (code "106") (name "/PE11_OUT") (class "Default")
      (node (ref "J2") (pin "16") (pinfunction "16_16") (pintype "passive"))
      (node (ref "U4") (pin "14") (pinfunction "B4_14") (pintype "passive"))
    )
    (net (code "109") (name "/PE13") (class "Default")
      (node (ref "R125") (pin "2") (pinfunction "2_2") (pintype "passive"))
      (node (ref "U2") (pin "2") (pinfunction "A0_2") (pintype "passive"))
    )
    (net (code "111") (name "/PE13_OUT") (class "Default")
      (node (ref "J1") (pin "18") (pinfunction "18_18") (pintype "passive"))
      (node (ref "U2") (pin "18") (pinfunction "B0_18") (pintype "passive"))
    )
    (net (code "112") (name "/PE14") (class "Default")
      (node (ref "R33") (pin "2") (pinfunction "2_2") (pintype "passive"))
      (node (ref "U2") (pin "4") (pinfunction "A2_4") (pintype "passive"))
    )
    (net (code "114") (name "/PE14_OUT") (class "Default")
      (node (ref "J1") (pin "16") (pinfunction "16_16") (pintype "passive"))
      (node (ref "U2") (pin "16") (pinfunction "B2_16") (pintype "passive"))
    )
    (net (code "121") (name "/PF3") (class "Default")
      (node (ref "R105") (pin "2") (pinfunction "2_2") (pintype "passive"))
      (node (ref "U5") (pin "2") (pinfunction "A0_2") (pintype "passive"))
    )
    (net (code "122") (name "/PF3_IN") (class "Default")
      (node (ref "P1") (pin "3") (pinfunction "3_3") (pintype "passive"))
      (node (ref "R139") (pin "2") (pinfunction "2_2") (pintype "passive"))
      (node (ref "U5") (pin "18") (pinfunction "B0_18") (pintype "passive"))
    )
    (net (code "123") (name "/PF3_INguang") (class "Default")
      (node (ref "P1") (pin "1") (pinfunction "1_1") (pintype "passive"))
      (node (ref "T4") (pin "13") (pinfunction "13_13") (pintype "passive"))
    )
    (net (code "124") (name "/PF6") (class "Default")
      (node (ref "R18") (pin "2") (pinfunction "2_2") (pintype "passive"))
      (node (ref "U4") (pin "5") (pinfunction "A3_5") (pintype "passive"))
    )
    (net (code "125") (name "/PF6_OUT") (class "Default")
      (node (ref "J1") (pin "4") (pinfunction "4_4") (pintype "passive"))
      (node (ref "J2") (pin "4") (pinfunction "4_4") (pintype "passive"))
      (node (ref "U4") (pin "15") (pinfunction "B3_15") (pintype "passive"))
    )
    (net (code "126") (name "/PF7") (class "Default")
      (node (ref "R21") (pin "2") (pinfunction "2_2") (pintype "passive"))
      (node (ref "U4") (pin "4") (pinfunction "A2_4") (pintype "passive"))
    )
    (net (code "127") (name "/PF7_OUT") (class "Default")
      (node (ref "J1") (pin "17") (pinfunction "17_17") (pintype "passive"))
      (node (ref "J2") (pin "17") (pinfunction "17_17") (pintype "passive"))
      (node (ref "U4") (pin "16") (pinfunction "B2_16") (pintype "passive"))
    )
    (net (code "128") (name "/PF8") (class "Default")
      (node (ref "R94") (pin "2") (pinfunction "2_2") (pintype "passive"))
      (node (ref "U4") (pin "8") (pinfunction "A6_8") (pintype "passive"))
    )
    (net (code "129") (name "/PF8_OUT") (class "Default")
      (node (ref "U4") (pin "12") (pinfunction "B6_12") (pintype "passive"))
    )
    (net (code "130") (name "/PF9") (class "Default")
      (node (ref "R17") (pin "2") (pinfunction "2_2") (pintype "passive"))
      (node (ref "U4") (pin "7") (pinfunction "A5_7") (pintype "passive"))
    )
    (net (code "131") (name "/PF9_OUT") (class "Default")
      (node (ref "J2") (pin "3") (pinfunction "3_3") (pintype "passive"))
      (node (ref "U4") (pin "13") (pinfunction "B5_13") (pintype "passive"))
    )
    (net (code "132") (name "/PF10") (class "Default")
      (node (ref "R93") (pin "2") (pinfunction "2_2") (pintype "passive"))
      (node (ref "U4") (pin "9") (pinfunction "A7_9") (pintype "passive"))
    )
    (net (code "133") (name "/PF10_OUT") (class "Default")
      (node (ref "U4") (pin "11") (pinfunction "B7_11") (pintype "passive"))
    )
    (net (code "134") (name "/PF12") (class "Default")
      (node (ref "U3") (pin "3") (pinfunction "A1_3") (pintype "passive"))
    )
    (net (code "135") (name "/PF12_IN") (class "Default")
      (node (ref "J1") (pin "22") (pinfunction "22_22") (pintype "passive"))
      (node (ref "R146") (pin "2") (pinfunction "2_2") (pintype "passive"))
      (node (ref "U3") (pin "17") (pinfunction "B1_17") (pintype "passive"))
    )
    (net (code "136") (name "/PF15") (class "Default")
      (node (ref "U3") (pin "2") (pinfunction "A0_2") (pintype "passive"))
    )
    (net (code "137") (name "/PF15_IN") (class "Default")
      (node (ref "J1") (pin "9") (pinfunction "9_9") (pintype "passive"))
      (node (ref "R147") (pin "2") (pinfunction "2_2") (pintype "passive"))
      (node (ref "U3") (pin "18") (pinfunction "B0_18") (pintype "passive"))
    )
    (net (code "138") (name "/SW2") (class "Default")
      (node (ref "J1") (pin "11") (pinfunction "11_11") (pintype "passive"))
      (node (ref "J2") (pin "11") (pinfunction "11_11") (pintype "passive"))
    )
    (net (code "139") (name "/hall_out_1") (class "Default")
      (node (ref "C27") (pin "1") (pinfunction "1_1") (pintype "passive"))
      (node (ref "R34") (pin "2") (pinfunction "2_2") (pintype "passive"))
      (node (ref "U20") (pin "3") (pinfunction "1IN+_3") (pintype "passive"))
    )
    (net (code "140") (name "/hall_out_2") (class "Default")
      (node (ref "C26") (pin "1") (pinfunction "1_1") (pintype "passive"))
      (node (ref "R35") (pin "2") (pinfunction "2_2") (pintype "passive"))
      (node (ref "U20") (pin "5") (pinfunction "1IN+_5") (pintype "passive"))
    )
    (net (code "141") (name "/hall_out_3") (class "Default")
      (node (ref "C4") (pin "1") (pinfunction "1_1") (pintype "passive"))
      (node (ref "R36") (pin "2") (pinfunction "2_2") (pintype "passive"))
      (node (ref "U21") (pin "3") (pinfunction "1IN+_3") (pintype "passive"))
    )
    (net (code "142") (name "/hall_out_4") (class "Default")
      (node (ref "C3") (pin "1") (pinfunction "1_1") (pintype "passive"))
      (node (ref "R37") (pin "2") (pinfunction "2_2") (pintype "passive"))
      (node (ref "U21") (pin "5") (pinfunction "1IN+_5") (pintype "passive"))
    )
    (net (code "143") (name "5_A_V") (class "Default")
      (node (ref "R140") (pin "1") (pinfunction "1_1") (pintype "passive"))
      (node (ref "R141") (pin "1") (pinfunction "1_1") (pintype "passive"))
      (node (ref "R142") (pin "1") (pinfunction "1_1") (pintype "passive"))
      (node (ref "R143") (pin "1") (pinfunction "1_1") (pintype "passive"))
      (node (ref "R144") (pin "1") (pinfunction "1_1") (pintype "passive"))
      (node (ref "R145") (pin "1") (pinfunction "1_1") (pintype "passive"))
      (node (ref "R146") (pin "1") (pinfunction "1_1") (pintype "passive"))
      (node (ref "R147") (pin "1") (pinfunction "1_1") (pintype "passive"))
      (node (ref "R38") (pin "1") (pinfunction "1_1") (pintype "passive"))
      (node (ref "R95") (pin "2") (pinfunction "2_2") (pintype "passive"))
      (node (ref "R96") (pin "2") (pinfunction "2_2") (pintype "passive"))
      (node (ref "T4") (pin "10") (pinfunction "10_10") (pintype "passive"))
      (node (ref "T4") (pin "12") (pinfunction "12_12") (pintype "passive"))
      (node (ref "T5") (pin "15") (pinfunction "15_15") (pintype "passive"))
      (node (ref "T5") (pin "16") (pinfunction "16_16") (pintype "passive"))
      (node (ref "U2") (pin "1") (pinfunction "DIR_1") (pintype "passive"))
      (node (ref "U2") (pin "20") (pinfunction "VCC_20") (pintype "passive"))
      (node (ref "U20") (pin "8") (pinfunction "VCC_8") (pintype "passive"))
      (node (ref "U21") (pin "8") (pinfunction "VCC_8") (pintype "passive"))
      (node (ref "U4") (pin "1") (pinfunction "DIR_1") (pintype "passive"))
      (node (ref "U4") (pin "20") (pinfunction "VCC_20") (pintype "passive"))
      (node (ref "U6") (pin "1") (pinfunction "DIR_1") (pintype "passive"))
      (node (ref "U6") (pin "20") (pinfunction "VCC_20") (pintype "passive"))
    )
    (net (code "144") (name "5_B_V") (class "Default")
      (node (ref "J1") (pin "8") (pinfunction "8_8") (pintype "passive"))
      (node (ref "J2") (pin "8") (pinfunction "8_8") (pintype "passive"))
    )
    (net (code "145") (name "12V") (class "Default")
      (node (ref "T4") (pin "1") (pinfunction "1_1") (pintype "passive"))
      (node (ref "T4") (pin "2") (pinfunction "2_2") (pintype "passive"))
      (node (ref "T5") (pin "1") (pinfunction "1_1") (pintype "passive"))
      (node (ref "T5") (pin "2") (pinfunction "2_2") (pintype "passive"))
    )
    (net (code "146") (name "GND") (class "Default")
      (node (ref "C26") (pin "2") (pinfunction "2_2") (pintype "passive"))
      (node (ref "C27") (pin "2") (pinfunction "2_2") (pintype "passive"))
      (node (ref "C3") (pin "2") (pinfunction "2_2") (pintype "passive"))
      (node (ref "C4") (pin "2") (pinfunction "2_2") (pintype "passive"))
      (node (ref "J1") (pin "21") (pinfunction "21_21") (pintype "passive"))
      (node (ref "J1") (pin "26") (pinfunction "26_26") (pintype "passive"))
      (node (ref "J1") (pin "27") (pinfunction "27_27") (pintype "passive"))
      (node (ref "J2") (pin "21") (pinfunction "21_21") (pintype "passive"))
      (node (ref "J2") (pin "26") (pinfunction "26_26") (pintype "passive"))
      (node (ref "J2") (pin "27") (pinfunction "27_27") (pintype "passive"))
      (node (ref "LED_IN0") (pin "2") (pinfunction "K_2") (pintype "passive"))
      (node (ref "LED_IN1") (pin "2") (pinfunction "K_2") (pintype "passive"))
      (node (ref "R125") (pin "1") (pinfunction "1_1") (pintype "passive"))
      (node (ref "R17") (pin "1") (pinfunction "1_1") (pintype "passive"))
      (node (ref "R18") (pin "1") (pinfunction "1_1") (pintype "passive"))
      (node (ref "R19") (pin "1") (pinfunction "1_1") (pintype "passive"))
      (node (ref "R20") (pin "1") (pinfunction "1_1") (pintype "passive"))
      (node (ref "R21") (pin "1") (pinfunction "1_1") (pintype "passive"))
      (node (ref "R22") (pin "1") (pinfunction "1_1") (pintype "passive"))
      (node (ref "R30") (pin "1") (pinfunction "1_1") (pintype "passive"))
      (node (ref "R31") (pin "1") (pinfunction "1_1") (pintype "passive"))
      (node (ref "R32") (pin "1") (pinfunction "1_1") (pintype "passive"))
      (node (ref "R33") (pin "1") (pinfunction "1_1") (pintype "passive"))
      (node (ref "R39") (pin "2") (pinfunction "2_2") (pintype "passive"))
      (node (ref "R41") (pin "1") (pinfunction "1_1") (pintype "passive"))
      (node (ref "R81") (pin "1") (pinfunction "1_1") (pintype "passive"))
      (node (ref "R82") (pin "1") (pinfunction "1_1") (pintype "passive"))
      (node (ref "R83") (pin "1") (pinfunction "1_1") (pintype "passive"))
      (node (ref "R84") (pin "1") (pinfunction "1_1") (pintype "passive"))
      (node (ref "R85") (pin "1") (pinfunction "1_1") (pintype "passive"))
      (node (ref "R86") (pin "1") (pinfunction "1_1") (pintype "passive"))
      (node (ref "R87") (pin "1") (pinfunction "1_1") (pintype "passive"))
      (node (ref "R88") (pin "1") (pinfunction "1_1") (pintype "passive"))
      (node (ref "R93") (pin "1") (pinfunction "1_1") (pintype "passive"))
      (node (ref "R94") (pin "1") (pinfunction "1_1") (pintype "passive"))
      (node (ref "T4") (pin "4") (pinfunction "4_4") (pintype "passive"))
      (node (ref "T4") (pin "6") (pinfunction "6_6") (pintype "passive"))
      (node (ref "T4") (pin "8") (pinfunction "8_8") (pintype "passive"))
      (node (ref "T5") (pin "14") (pinfunction "14_14") (pintype "passive"))
      (node (ref "T5") (pin "8") (pinfunction "8_8") (pintype "passive"))
      (node (ref "U2") (pin "10") (pinfunction "GND_10") (pintype "passive"))
      (node (ref "U2") (pin "19") (pinfunction "OE#_19") (pintype "passive"))
      (node (ref "U20") (pin "4") (pinfunction "GND_4") (pintype "passive"))
      (node (ref "U21") (pin "4") (pinfunction "GND_4") (pintype "passive"))
      (node (ref "U3") (pin "1") (pinfunction "DIR_1") (pintype "passive"))
      (node (ref "U3") (pin "10") (pinfunction "GND_10") (pintype "passive"))
      (node (ref "U3") (pin "19") (pinfunction "OE#_19") (pintype "passive"))
      (node (ref "U4") (pin "10") (pinfunction "GND_10") (pintype "passive"))
      (node (ref "U4") (pin "19") (pinfunction "OE#_19") (pintype "passive"))
      (node (ref "U5") (pin "1") (pinfunction "DIR_1") (pintype "passive"))
      (node (ref "U5") (pin "10") (pinfunction "GND_10") (pintype "passive"))
      (node (ref "U5") (pin "19") (pinfunction "OE#_19") (pintype "passive"))
      (node (ref "U6") (pin "10") (pinfunction "GND_10") (pintype "passive"))
      (node (ref "U6") (pin "19") (pinfunction "OE#_19") (pintype "passive"))
    )
    (net (code "147") (name "Net-(LED_IN0-A)") (class "Default")
      (node (ref "LED_IN0") (pin "1") (pinfunction "A_1") (pintype "passive"))
      (node (ref "R42") (pin "1") (pinfunction "1_1") (pintype "passive"))
    )
    (net (code "148") (name "Net-(LED_IN1-A)") (class "Default")
      (node (ref "LED_IN1") (pin "1") (pinfunction "A_1") (pintype "passive"))
      (node (ref "R43") (pin "1") (pinfunction "1_1") (pintype "passive"))
    )
    (net (code "149") (name "Net-(P1-Pad2)") (class "Default")
      (node (ref "P1") (pin "2") (pinfunction "2_2") (pintype "passive"))
      (node (ref "R42") (pin "2") (pinfunction "2_2") (pintype "passive"))
    )
    (net (code "150") (name "Net-(P1-Pad4)") (class "Default")
      (node (ref "P1") (pin "4") (pinfunction "4_4") (pintype "passive"))
      (node (ref "R95") (pin "1") (pinfunction "1_1") (pintype "passive"))
    )
    (net (code "151") (name "Net-(P2-Pad2)") (class "Default")
      (node (ref "P2") (pin "2") (pinfunction "2_2") (pintype "passive"))
      (node (ref "R43") (pin "2") (pinfunction "2_2") (pintype "passive"))
    )
    (net (code "152") (name "Net-(P2-Pad4)") (class "Default")
      (node (ref "P2") (pin "4") (pinfunction "4_4") (pintype "passive"))
      (node (ref "R96") (pin "1") (pinfunction "1_1") (pintype "passive"))
    )
    (net (code "153") (name "Net-(R107-Pad1)") (class "Default")
      (node (ref "R107") (pin "1") (pinfunction "1_1") (pintype "passive"))
      (node (ref "R108") (pin "1") (pinfunction "1_1") (pintype "passive"))
      (node (ref "R134") (pin "1") (pinfunction "1_1") (pintype "passive"))
      (node (ref "R135") (pin "1") (pinfunction "1_1") (pintype "passive"))
      (node (ref "R137") (pin "1") (pinfunction "1_1") (pintype "passive"))
      (node (ref "R138") (pin "1") (pinfunction "1_1") (pintype "passive"))
      (node (ref "R139") (pin "1") (pinfunction "1_1") (pintype "passive"))
      (node (ref "R40") (pin "2") (pinfunction "2_2") (pintype "passive"))
      (node (ref "R41") (pin "2") (pinfunction "2_2") (pintype "passive"))
    )
    (net (code "154") (name "unconnected-(U2-A5-Pad7)") (class "Default")
      (node (ref "U2") (pin "7") (pinfunction "A5_7") (pintype "passive"))
    )
    (net (code "155") (name "unconnected-(U2-A6-Pad8)") (class "Default")
      (node (ref "U2") (pin "8") (pinfunction "A6_8") (pintype "passive"))
    )
    (net (code "156") (name "unconnected-(U2-A7-Pad9)") (class "Default")
      (node (ref "U2") (pin "9") (pinfunction "A7_9") (pintype "passive"))
    )
    (net (code "157") (name "unconnected-(U2-B5-Pad13)") (class "Default")
      (node (ref "U2") (pin "13") (pinfunction "B5_13") (pintype "passive"))
    )
    (net (code "158") (name "unconnected-(U2-B6-Pad12)") (class "Default")
      (node (ref "U2") (pin "12") (pinfunction "B6_12") (pintype "passive"))
    )
    (net (code "159") (name "unconnected-(U2-B7-Pad11)") (class "Default")
      (node (ref "U2") (pin "11") (pinfunction "B7_11") (pintype "passive"))
    )
    (net (code "160") (name "unconnected-(U5-A7-Pad9)") (class "Default")
      (node (ref "U5") (pin "9") (pinfunction "A7_9") (pintype "passive"))
    )
    (net (code "161") (name "unconnected-(U5-B7-Pad11)") (class "Default")
      (node (ref "U5") (pin "11") (pinfunction "B7_11") (pintype "passive"))
    )
  )
)
